# FAN_CTRL.net
KiCad netlist of a schematic drawn in Altium Designer
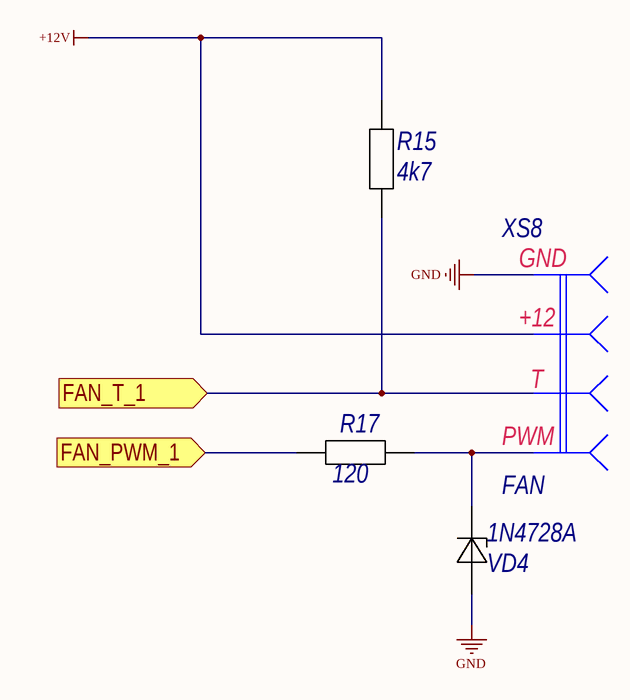
[diagram p0: FAN_CTRL.SchDoc]

(export (version "E")
  (design (tool "Eeschema 10.0.6"))
  (components
    (comp (ref "R15")
      (value "4k7")
      (footprint "C0805R")
      (fields (field (name "PUBLISHER") "Andrew Danich"))
      (libsource (lib "PA_control_board") (part "RES_0805"))
    )
    (comp (ref "R17")
      (value "120")
      (footprint "C0805R")
      (fields (field (name "PUBLISHER") "Andrew Danich"))
      (libsource (lib "PA_control_board") (part "RES_0805"))
    )
    (comp (ref "VD4")
      (value "1N4728A")
      (footprint "DO-41")
      (fields (field (name "PUBLISHER") "Andrew Danich"))
      (libsource (lib "PA_control_board") (part "1N4728A"))
    )
    (comp (ref "XS8")
      (value "FAN")
      (footprint "WF-4")
      (fields (field (name "PUBLISHER") "Andrew Danich"))
      (libsource (lib "PA_control_board") (part "FAN_CON"))
    )
  )
  (nets
    (net (code "1") (name "+12V") (class "Default")
      (node (ref "R15") (pin "2") (pinfunction "2_2") (pintype "passive"))
      (node (ref "XS8") (pin "2") (pintype "passive"))
    )
    (net (code "2") (name "/FAN_PWM_1") (class "Default")
      (node (ref "R17") (pin "1") (pinfunction "1_1") (pintype "passive"))
    )
    (net (code "3") (name "/FAN_T_1") (class "Default")
      (node (ref "R15") (pin "1") (pinfunction "1_1") (pintype "passive"))
      (node (ref "XS8") (pin "3") (pintype "passive"))
    )
    (net (code "4") (name "GND") (class "Default")
      (node (ref "VD4") (pin "1") (pinfunction "А_1") (pintype "passive"))
      (node (ref "XS8") (pin "1") (pintype "passive"))
    )
    (net (code "5") (name "Net-(VD4-К)") (class "Default")
      (node (ref "R17") (pin "2") (pinfunction "2_2") (pintype "passive"))
      (node (ref "VD4") (pin "2") (pinfunction "К_2") (pintype "passive"))
      (node (ref "XS8") (pin "4") (pintype "passive"))
    )
  )
)
